# nrf52_dev.net
KiCad netlist of a schematic drawn in EAGLE
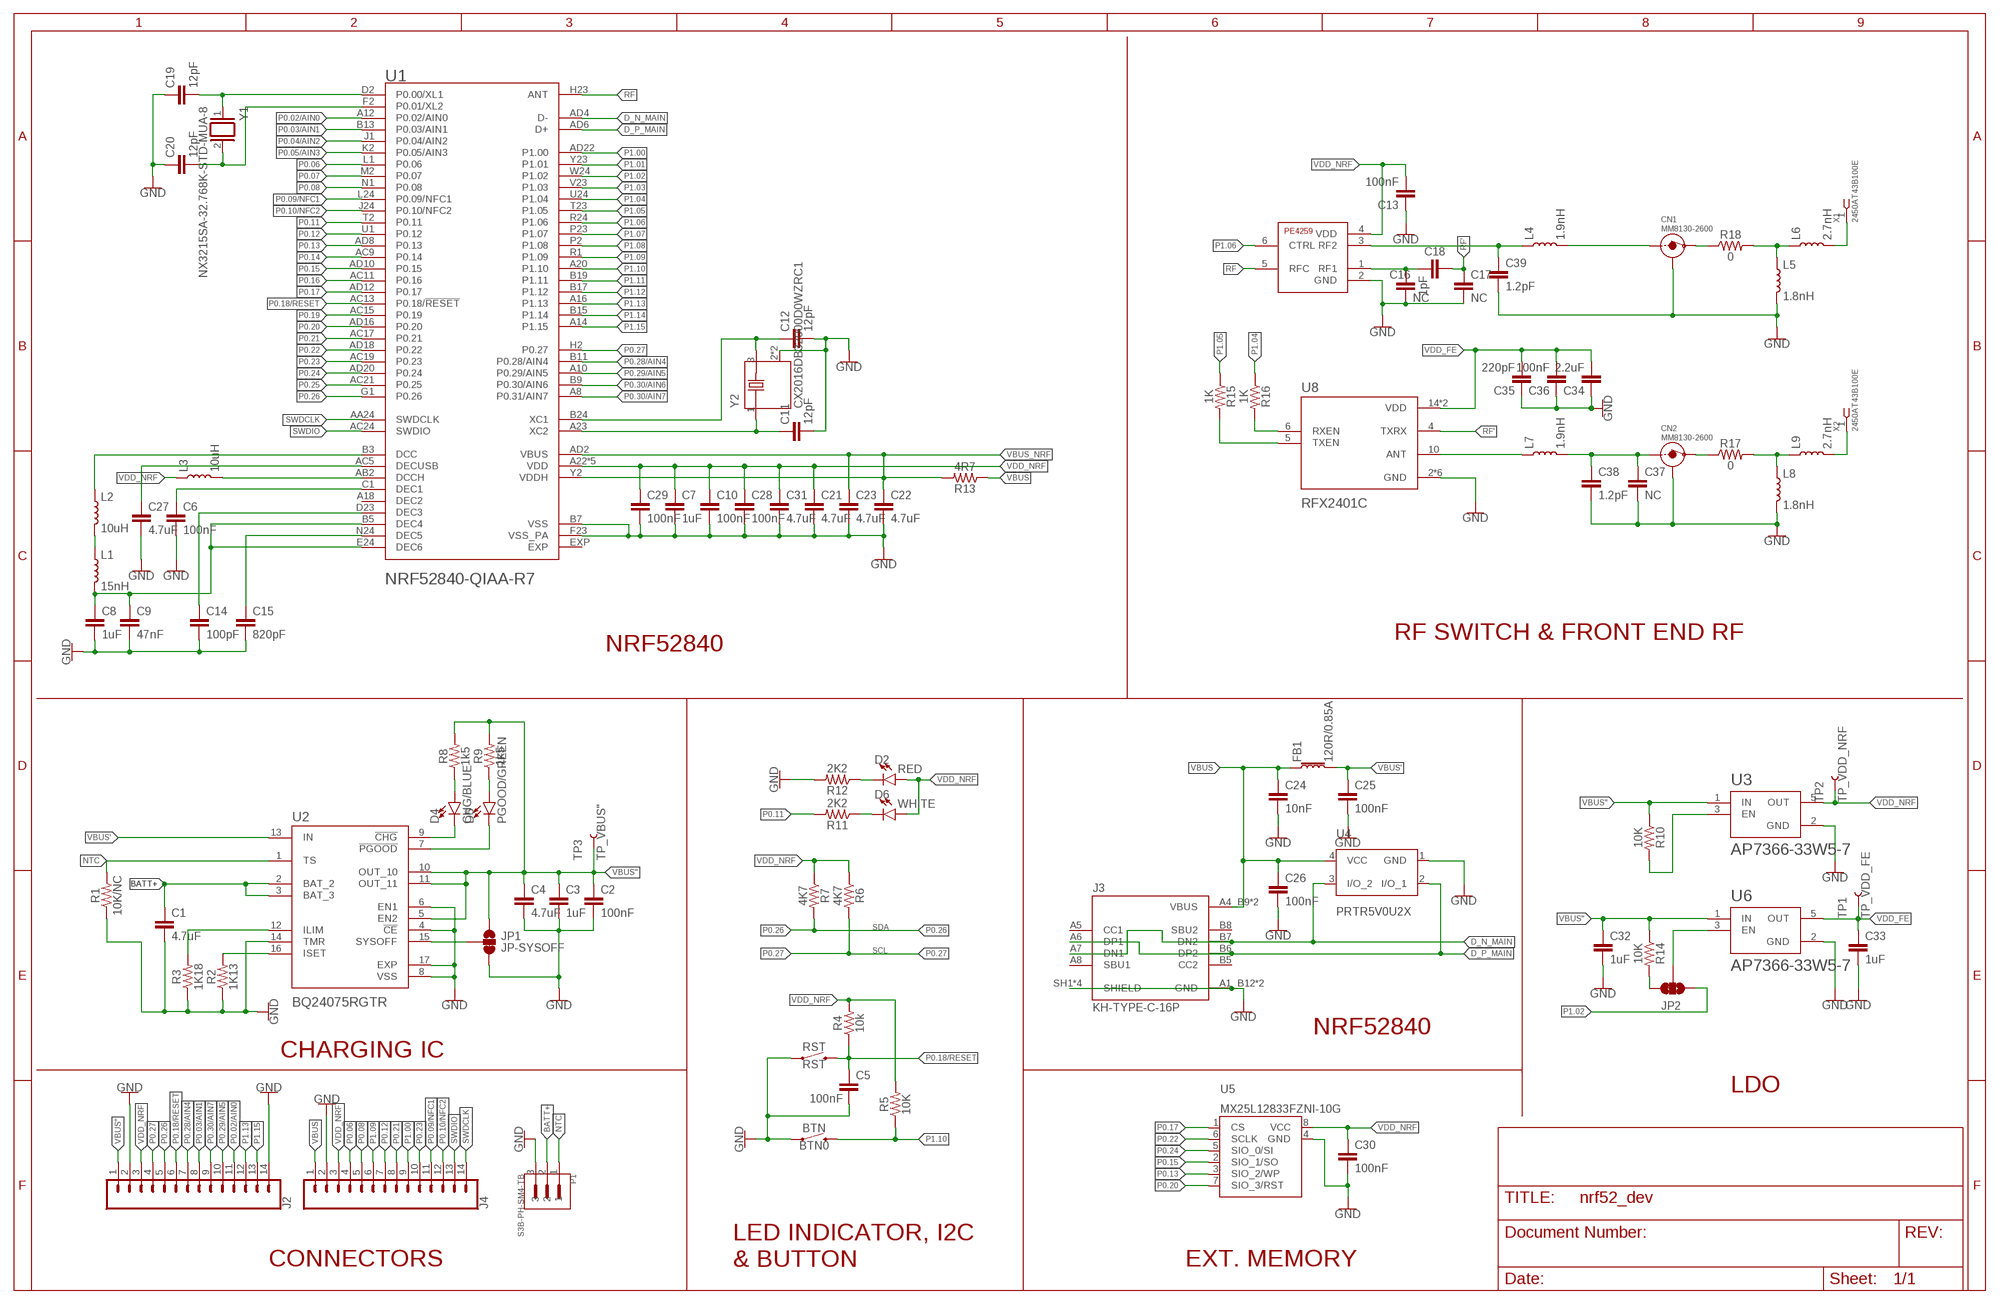
[diagram p0: schematic, sheet 1]

(export (version "E")
  (design (tool "Eeschema 10.0.6"))
  (components
    (comp (ref "BTN")
      (value "BTN0")
      (footprint "eagle-import:TACTILE_SWITCH_SMD_6.0X3.5MM")
      (libsource (lib "eagle-import") (part "MOMENTARY-SWITCH-SPST-SMD-6.0X3.5MM"))
    )
    (comp (ref "C1")
      (value "4.7uF")
      (footprint "eagle-import:0805")
      (libsource (lib "eagle-import") (part "4.7UF-0805-50V-(10%)"))
    )
    (comp (ref "C2")
      (value "100nF")
      (footprint "eagle-import:0603")
      (libsource (lib "eagle-import") (part "0.1UF-0603-25V-(+80/-20%)"))
    )
    (comp (ref "C3")
      (value "1uF")
      (footprint "eagle-import:0603")
      (libsource (lib "eagle-import") (part "0.1UF-0603-25V-(+80/-20%)"))
    )
    (comp (ref "C4")
      (value "4.7uF")
      (footprint "eagle-import:0805")
      (libsource (lib "eagle-import") (part "4.7UF-0805-50V-(10%)"))
    )
    (comp (ref "C5")
      (value "100nF")
      (footprint "eagle-import:0402")
      (libsource (lib "eagle-import") (part "0.1UF-0402-10V-10%-X7R"))
    )
    (comp (ref "C6")
      (value "100nF")
      (footprint "eagle-import:0402")
      (libsource (lib "eagle-import") (part "0.1UF-0402-10V-10%-X7R"))
    )
    (comp (ref "C7")
      (value "1uF")
      (footprint "eagle-import:0402")
      (libsource (lib "eagle-import") (part "0.1UF-0402-10V-10%-X7R"))
    )
    (comp (ref "C8")
      (value "1uF")
      (footprint "eagle-import:0402")
      (libsource (lib "eagle-import") (part "0.1UF-0402-10V-10%-X7R"))
    )
    (comp (ref "C9")
      (value "47nF")
      (footprint "eagle-import:0402")
      (libsource (lib "eagle-import") (part "0.1UF-0402-10V-10%-X7R"))
    )
    (comp (ref "C10")
      (value "100nF")
      (footprint "eagle-import:0402")
      (libsource (lib "eagle-import") (part "0.1UF-0402-10V-10%-X7R"))
    )
    (comp (ref "C11")
      (value "12pF")
      (footprint "eagle-import:0603")
      (libsource (lib "eagle-import") (part "0.1UF-0603-25V-(+80/-20%)"))
    )
    (comp (ref "C12")
      (value "12pF")
      (footprint "eagle-import:0603")
      (libsource (lib "eagle-import") (part "0.1UF-0603-25V-(+80/-20%)"))
    )
    (comp (ref "C13")
      (value "100nF")
      (footprint "eagle-import:0402")
      (libsource (lib "eagle-import") (part "0.1UF-0402-10V-10%-X7R"))
    )
    (comp (ref "C14")
      (value "100pF")
      (footprint "eagle-import:0402")
      (libsource (lib "eagle-import") (part "0.1UF-0402-10V-10%-X7R"))
    )
    (comp (ref "C15")
      (value "820pF")
      (footprint "eagle-import:0402")
      (libsource (lib "eagle-import") (part "0.1UF-0402-10V-10%-X7R"))
    )
    (comp (ref "C16")
      (value "NC")
      (footprint "eagle-import:0402")
      (libsource (lib "eagle-import") (part "0.1UF-0402-10V-10%-X7R"))
    )
    (comp (ref "C17")
      (value "NC")
      (footprint "eagle-import:0402")
      (libsource (lib "eagle-import") (part "0.1UF-0402-10V-10%-X7R"))
    )
    (comp (ref "C18")
      (value "1pF")
      (footprint "eagle-import:0603")
      (libsource (lib "eagle-import") (part "0.1UF-0603-25V-(+80/-20%)"))
    )
    (comp (ref "C19")
      (value "12pF")
      (footprint "eagle-import:0402")
      (libsource (lib "eagle-import") (part "0.1UF-0402-10V-10%-X7R"))
    )
    (comp (ref "C20")
      (value "12pF")
      (footprint "eagle-import:0402")
      (libsource (lib "eagle-import") (part "0.1UF-0402-10V-10%-X7R"))
    )
    (comp (ref "C21")
      (value "4.7uF")
      (footprint "eagle-import:0402")
      (libsource (lib "eagle-import") (part "0.1UF-0402-10V-10%-X7R"))
    )
    (comp (ref "C22")
      (value "4.7uF")
      (footprint "eagle-import:0402")
      (libsource (lib "eagle-import") (part "0.1UF-0402-10V-10%-X7R"))
    )
    (comp (ref "C23")
      (value "4.7uF")
      (footprint "eagle-import:0402")
      (libsource (lib "eagle-import") (part "0.1UF-0402-10V-10%-X7R"))
    )
    (comp (ref "C24")
      (value "10nF")
      (footprint "eagle-import:0402")
      (libsource (lib "eagle-import") (part "0.1UF-0402-10V-10%-X7R"))
    )
    (comp (ref "C25")
      (value "100nF")
      (footprint "eagle-import:0402")
      (libsource (lib "eagle-import") (part "0.1UF-0402-10V-10%-X7R"))
    )
    (comp (ref "C26")
      (value "100nF")
      (footprint "eagle-import:0402")
      (libsource (lib "eagle-import") (part "0.1UF-0402-10V-10%-X7R"))
    )
    (comp (ref "C27")
      (value "4.7uF")
      (footprint "eagle-import:0603")
      (libsource (lib "eagle-import") (part "0.1UF-0603-25V-(+80/-20%)"))
    )
    (comp (ref "C28")
      (value "100nF")
      (footprint "eagle-import:0402")
      (libsource (lib "eagle-import") (part "0.1UF-0402-10V-10%-X7R"))
    )
    (comp (ref "C29")
      (value "100nF")
      (footprint "eagle-import:0402")
      (libsource (lib "eagle-import") (part "0.1UF-0402-10V-10%-X7R"))
    )
    (comp (ref "C30")
      (value "100nF")
      (footprint "eagle-import:0402")
      (libsource (lib "eagle-import") (part "0.1UF-0402-10V-10%-X7R"))
    )
    (comp (ref "C31")
      (value "4.7uF")
      (footprint "eagle-import:0402")
      (libsource (lib "eagle-import") (part "0.1UF-0402-10V-10%-X7R"))
    )
    (comp (ref "C32")
      (value "1uF")
      (footprint "eagle-import:0603")
      (libsource (lib "eagle-import") (part "0.1UF-0603-25V-(+80/-20%)"))
    )
    (comp (ref "C33")
      (value "1uF")
      (footprint "eagle-import:0603")
      (libsource (lib "eagle-import") (part "0.1UF-0603-25V-(+80/-20%)"))
    )
    (comp (ref "C34")
      (value "2.2uF")
      (footprint "eagle-import:0402")
      (libsource (lib "eagle-import") (part "0.1UF-0402-10V-10%-X7R"))
    )
    (comp (ref "C35")
      (value "220pF")
      (footprint "eagle-import:0402")
      (libsource (lib "eagle-import") (part "0.1UF-0402-10V-10%-X7R"))
    )
    (comp (ref "C36")
      (value "100nF")
      (footprint "eagle-import:0402")
      (libsource (lib "eagle-import") (part "0.1UF-0402-10V-10%-X7R"))
    )
    (comp (ref "C37")
      (value "NC")
      (footprint "eagle-import:0402")
      (libsource (lib "eagle-import") (part "0.1UF-0402-10V-10%-X7R"))
    )
    (comp (ref "C38")
      (value "1.2pF")
      (footprint "eagle-import:0402")
      (libsource (lib "eagle-import") (part "0.1UF-0402-10V-10%-X7R"))
    )
    (comp (ref "C39")
      (value "1.2pF")
      (footprint "eagle-import:0402")
      (libsource (lib "eagle-import") (part "0.1UF-0402-10V-10%-X7R"))
    )
    (comp (ref "CN1")
      (value "MM8130-2600")
      (footprint "eagle-import:MM8130-2600")
      (fields (field (name "MF") "Murata"))
      (libsource (lib "eagle-import") (part "MM8130-2600"))
    )
    (comp (ref "CN2")
      (value "MM8130-2600")
      (footprint "eagle-import:MM8130-2600")
      (fields (field (name "MF") "Murata"))
      (libsource (lib "eagle-import") (part "MM8130-2600"))
    )
    (comp (ref "D2")
      (value "RED")
      (footprint "eagle-import:LED-0603")
      (libsource (lib "eagle-import") (part "LED0603"))
    )
    (comp (ref "D4")
      (value "CHG/BLUE")
      (footprint "eagle-import:LED-0603")
      (libsource (lib "eagle-import") (part "LED0603"))
    )
    (comp (ref "D5")
      (value "PGOOD/GREEN")
      (footprint "eagle-import:LED-0603")
      (libsource (lib "eagle-import") (part "LED0603"))
    )
    (comp (ref "D6")
      (value "WHITE")
      (footprint "eagle-import:LED-0603")
      (libsource (lib "eagle-import") (part "LED0603"))
    )
    (comp (ref "FB1")
      (value "120R/0.85A")
      (footprint "eagle-import:0402")
      (libsource (lib "eagle-import") (part "FERRITE_BEAD"))
    )
    (comp (ref "J2")
      (value "CONN_14NO_SILK")
      (footprint "eagle-import:1X14_NO_SILK")
      (libsource (lib "eagle-import") (part "CONN_14NO_SILK"))
    )
    (comp (ref "J3")
      (value "KH-TYPE-C-16P")
      (footprint "eagle-import:KINGHELM_KH-TYPE-C-16P")
      (fields (field (name "MF") "kinghelm"))
      (libsource (lib "eagle-import") (part "KH-TYPE-C-16P"))
    )
    (comp (ref "J4")
      (value "CONN_14NO_SILK")
      (footprint "eagle-import:1X14_NO_SILK")
      (libsource (lib "eagle-import") (part "CONN_14NO_SILK"))
    )
    (comp (ref "JP1")
      (value "JP-SYSOFF")
      (footprint "eagle-import:SMT-JUMPER_3_1-NC_TRACE_SILK")
      (libsource (lib "eagle-import") (part "JUMPER-SMT_3_1-NC_TRACE_SILK"))
    )
    (comp (ref "JP2")
      (value "JP_EN1")
      (footprint "eagle-import:SMT-JUMPER_3_1-NC_TRACE_SILK")
      (libsource (lib "eagle-import") (part "JUMPER-SMT_3_1-NC_TRACE_SILK"))
    )
    (comp (ref "L1")
      (value "15nH")
      (footprint "eagle-import:0402")
      (libsource (lib "eagle-import") (part "INDUCTOR-0402-3.9NH"))
    )
    (comp (ref "L2")
      (value "10uH")
      (footprint "eagle-import:0603")
      (libsource (lib "eagle-import") (part "39NH-0603"))
    )
    (comp (ref "L3")
      (value "10uH")
      (footprint "eagle-import:0603")
      (libsource (lib "eagle-import") (part "39NH-0603"))
    )
    (comp (ref "L4")
      (value "1.9nH")
      (footprint "eagle-import:0402")
      (libsource (lib "eagle-import") (part "INDUCTOR-0402-3.9NH"))
    )
    (comp (ref "L5")
      (value "1.8nH")
      (footprint "eagle-import:0603")
      (libsource (lib "eagle-import") (part "39NH-0603"))
    )
    (comp (ref "L6")
      (value "2.7nH")
      (footprint "eagle-import:0603")
      (libsource (lib "eagle-import") (part "39NH-0603"))
    )
    (comp (ref "L7")
      (value "1.9nH")
      (footprint "eagle-import:0402")
      (libsource (lib "eagle-import") (part "INDUCTOR-0402-3.9NH"))
    )
    (comp (ref "L8")
      (value "1.8nH")
      (footprint "eagle-import:0603")
      (libsource (lib "eagle-import") (part "39NH-0603"))
    )
    (comp (ref "L9")
      (value "2.7nH")
      (footprint "eagle-import:0603")
      (libsource (lib "eagle-import") (part "39NH-0603"))
    )
    (comp (ref "P1")
      (value "S3B-PH-SM4-TB")
      (footprint "eagle-import:JST_S3B-PH-SM4-TB")
      (fields (field (name "MF") "JST Sales"))
      (libsource (lib "eagle-import") (part "S3B-PH-SM4-TB"))
    )
    (comp (ref "R1")
      (value "10K/NC")
      (footprint "eagle-import:0603")
      (libsource (lib "eagle-import") (part "RESISTOR0603"))
    )
    (comp (ref "R2")
      (value "1K13")
      (footprint "eagle-import:0603")
      (libsource (lib "eagle-import") (part "RESISTOR0603"))
    )
    (comp (ref "R3")
      (value "1K18")
      (footprint "eagle-import:0603")
      (libsource (lib "eagle-import") (part "RESISTOR0603"))
    )
    (comp (ref "R4")
      (value "10k")
      (footprint "eagle-import:0402")
      (libsource (lib "eagle-import") (part "RESISTOR0402"))
    )
    (comp (ref "R5")
      (value "10K")
      (footprint "eagle-import:0402")
      (libsource (lib "eagle-import") (part "RESISTOR0402"))
    )
    (comp (ref "R6")
      (value "4K7")
      (footprint "eagle-import:0402")
      (libsource (lib "eagle-import") (part "0OHM-0402-1/10W"))
    )
    (comp (ref "R7")
      (value "4K7")
      (footprint "eagle-import:0402")
      (libsource (lib "eagle-import") (part "0OHM-0402-1/10W"))
    )
    (comp (ref "R8")
      (value "1k5")
      (footprint "eagle-import:0402")
      (libsource (lib "eagle-import") (part "0OHM-0402-1/10W"))
    )
    (comp (ref "R9")
      (value "1k5")
      (footprint "eagle-import:0402")
      (libsource (lib "eagle-import") (part "0OHM-0402-1/10W"))
    )
    (comp (ref "R10")
      (value "10K")
      (footprint "eagle-import:0603")
      (libsource (lib "eagle-import") (part "RESISTOR0603"))
    )
    (comp (ref "R11")
      (value "2K2")
      (footprint "eagle-import:0402")
      (libsource (lib "eagle-import") (part "0OHM-0402-1/10W"))
    )
    (comp (ref "R12")
      (value "2K2")
      (footprint "eagle-import:0402")
      (libsource (lib "eagle-import") (part "0OHM-0402-1/10W"))
    )
    (comp (ref "R13")
      (value "4R7")
      (footprint "eagle-import:0603")
      (libsource (lib "eagle-import") (part "RESISTOR0603"))
    )
    (comp (ref "R14")
      (value "10K")
      (footprint "eagle-import:0603")
      (libsource (lib "eagle-import") (part "RESISTOR0603"))
    )
    (comp (ref "R15")
      (value "1K")
      (footprint "eagle-import:0402")
      (libsource (lib "eagle-import") (part "0OHM-0402-1/10W"))
    )
    (comp (ref "R16")
      (value "1K")
      (footprint "eagle-import:0402")
      (libsource (lib "eagle-import") (part "0OHM-0402-1/10W"))
    )
    (comp (ref "R17")
      (value "0")
      (footprint "eagle-import:0402")
      (libsource (lib "eagle-import") (part "0OHM-0402-1/10W"))
    )
    (comp (ref "R18")
      (value "0")
      (footprint "eagle-import:0402")
      (libsource (lib "eagle-import") (part "0OHM-0402-1/10W"))
    )
    (comp (ref "RST")
      (value "RST")
      (footprint "eagle-import:TACTILE_SWITCH_SMD_6.0X3.5MM")
      (libsource (lib "eagle-import") (part "MOMENTARY-SWITCH-SPST-SMD-6.0X3.5MM"))
    )
    (comp (ref "TP1")
      (value "TP_VDD_FE")
      (footprint "eagle-import:PAD.03X.04")
      (libsource (lib "eagle-import") (part "TEST-POINT3X4"))
    )
    (comp (ref "TP2")
      (value "TP_VDD_NRF")
      (footprint "eagle-import:PAD.03X.04")
      (libsource (lib "eagle-import") (part "TEST-POINT3X4"))
    )
    (comp (ref "TP3")
      (value "TP_VBUS''")
      (footprint "eagle-import:PAD.03X.04")
      (libsource (lib "eagle-import") (part "TEST-POINT3X4"))
    )
    (comp (ref "U1")
      (value "NRF52840-QIAA-R7")
      (footprint "eagle-import:NORDIC_NRF52840-QIAA-R7")
      (fields (field (name "MF") "Nordic Semiconductor"))
      (libsource (lib "eagle-import") (part "NRF52840-QIAA-R7"))
    )
    (comp (ref "U2")
      (value "BQ24075RGTR")
      (footprint "eagle-import:QFN50P300X300X100-17N")
      (fields (field (name "DIGI-KEY_PART_NUMBER") "296-38874-2-ND") (field (name "MF") "Texas Instruments"))
      (libsource (lib "eagle-import") (part "BQ24075RGTR"))
    )
    (comp (ref "U3")
      (value "AP7366-33W5-7")
      (footprint "eagle-import:SOT95P285X140-5N")
      (fields (field (name "MF") "Diodes Zetex"))
      (libsource (lib "eagle-import") (part "AP7366-33W5-7"))
    )
    (comp (ref "U4")
      (value "PRTR5V0U2X")
      (footprint "eagle-import:SOT190P230X110-4N")
      (fields (field (name "MF") "Nexperia USA"))
      (libsource (lib "eagle-import") (part "PRTR5V0U2X"))
    )
    (comp (ref "U5")
      (value "MX25L12833FZNI-10G")
      (footprint "eagle-import:SON127P500X600X80-9N")
      (libsource (lib "eagle-import") (part "MX25L12833FZNI-10G"))
    )
    (comp (ref "U6")
      (value "AP7366-33W5-7")
      (footprint "eagle-import:SOT95P285X140-5N")
      (fields (field (name "MF") "Diodes Zetex"))
      (libsource (lib "eagle-import") (part "AP7366-33W5-7"))
    )
    (comp (ref "U7")
      (value "PE4259")
      (footprint "eagle-import:SOT65P210X110-6N")
      (libsource (lib "eagle-import") (part "PE4259"))
    )
    (comp (ref "U8")
      (value "RFX2401C")
      (footprint "eagle-import:QFN50P300X300X60-17N")
      (fields (field (name "MF") "Skyworks Solutions"))
      (libsource (lib "eagle-import") (part "RFX2401C"))
    )
    (comp (ref "X1")
      (value "2450AT43B100E")
      (footprint "eagle-import:2450AT43B100")
      (fields (field (name "MF") "Johanson"))
      (libsource (lib "eagle-import") (part "2450AT43B100E"))
    )
    (comp (ref "X2")
      (value "2450AT43B100E")
      (footprint "eagle-import:2450AT43B100")
      (fields (field (name "MF") "Johanson"))
      (libsource (lib "eagle-import") (part "2450AT43B100E"))
    )
    (comp (ref "Y1")
      (value "NX3215SA-32.768K-STD-MUA-8")
      (footprint "eagle-import:XTAL_NX3215SA-32.768K-STD-MUA-8")
      (fields (field (name "DIGI-KEY_PART_NUMBER") "644-1156-2-ND") (field (name "MF") "NDK America,"))
      (libsource (lib "eagle-import") (part "NX3215SA-32.768K-STD-MUA-8"))
    )
    (comp (ref "Y2")
      (value "CX2016DB32000D0WZRC1")
      (footprint "eagle-import:OSCCC200X160X45N")
      (fields (field (name "MF") "Kyocera International"))
      (libsource (lib "eagle-import") (part "CX2016DB32000D0WZRC1"))
    )
  )
  (nets
    (net (code "1") (name "/DEC2") (class "Default")
      (node (ref "U1") (pin "A18") (pinfunction "DEC2_A18") (pintype "power_in"))
    )
    (net (code "2") (name "/EXP") (class "Default")
      (node (ref "U1") (pin "EXP") (pinfunction "EXP_EXP") (pintype "power_in"))
    )
    (net (code "3") (name "BATT+") (class "Default")
      (node (ref "C1") (pin "1") (pinfunction "1_1") (pintype "passive"))
      (node (ref "P1") (pin "2") (pinfunction "2_2") (pintype "passive"))
      (node (ref "U2") (pin "2") (pinfunction "BAT_2_2") (pintype "bidirectional"))
      (node (ref "U2") (pin "3") (pinfunction "BAT_3_3") (pintype "bidirectional"))
    )
    (net (code "4") (name "D_N_MAIN") (class "Default")
      (node (ref "J3") (pin "A7") (pinfunction "DN1_A7") (pintype "bidirectional"))
      (node (ref "J3") (pin "B7") (pinfunction "DN2_B7") (pintype "bidirectional"))
      (node (ref "U1") (pin "AD4") (pinfunction "D-_AD4") (pintype "bidirectional"))
      (node (ref "U4") (pin "3") (pinfunction "I/O_2_3") (pintype "passive"))
    )
    (net (code "5") (name "D_P_MAIN") (class "Default")
      (node (ref "J3") (pin "A6") (pinfunction "DP1_A6") (pintype "bidirectional"))
      (node (ref "J3") (pin "B6") (pinfunction "DP2_B6") (pintype "bidirectional"))
      (node (ref "U1") (pin "AD6") (pinfunction "D+_AD6") (pintype "bidirectional"))
      (node (ref "U4") (pin "2") (pinfunction "I/O_1_2") (pintype "passive"))
    )
    (net (code "6") (name "GND") (class "Default")
      (node (ref "BTN") (pin "1") (pinfunction "1_1") (pintype "passive"))
      (node (ref "C1") (pin "2") (pinfunction "2_2") (pintype "passive"))
      (node (ref "C10") (pin "2") (pinfunction "2_2") (pintype "passive"))
      (node (ref "C11") (pin "2") (pinfunction "2_2") (pintype "passive"))
      (node (ref "C12") (pin "2") (pinfunction "2_2") (pintype "passive"))
      (node (ref "C13") (pin "1") (pinfunction "1_1") (pintype "passive"))
      (node (ref "C14") (pin "2") (pinfunction "2_2") (pintype "passive"))
      (node (ref "C15") (pin "2") (pinfunction "2_2") (pintype "passive"))
      (node (ref "C16") (pin "2") (pinfunction "2_2") (pintype "passive"))
      (node (ref "C17") (pin "2") (pinfunction "2_2") (pintype "passive"))
      (node (ref "C19") (pin "1") (pinfunction "1_1") (pintype "passive"))
      (node (ref "C2") (pin "2") (pinfunction "2_2") (pintype "passive"))
      (node (ref "C20") (pin "1") (pinfunction "1_1") (pintype "passive"))
      (node (ref "C21") (pin "2") (pinfunction "2_2") (pintype "passive"))
      (node (ref "C22") (pin "2") (pinfunction "2_2") (pintype "passive"))
      (node (ref "C23") (pin "2") (pinfunction "2_2") (pintype "passive"))
      (node (ref "C24") (pin "2") (pinfunction "2_2") (pintype "passive"))
      (node (ref "C25") (pin "2") (pinfunction "2_2") (pintype "passive"))
      (node (ref "C26") (pin "2") (pinfunction "2_2") (pintype "passive"))
      (node (ref "C27") (pin "2") (pinfunction "2_2") (pintype "passive"))
      (node (ref "C28") (pin "2") (pinfunction "2_2") (pintype "passive"))
      (node (ref "C29") (pin "2") (pinfunction "2_2") (pintype "passive"))
      (node (ref "C3") (pin "2") (pinfunction "2_2") (pintype "passive"))
      (node (ref "C30") (pin "2") (pinfunction "2_2") (pintype "passive"))
      (node (ref "C31") (pin "2") (pinfunction "2_2") (pintype "passive"))
      (node (ref "C32") (pin "2") (pinfunction "2_2") (pintype "passive"))
      (node (ref "C33") (pin "2") (pinfunction "2_2") (pintype "passive"))
      (node (ref "C34") (pin "1") (pinfunction "1_1") (pintype "passive"))
      (node (ref "C35") (pin "1") (pinfunction "1_1") (pintype "passive"))
      (node (ref "C36") (pin "1") (pinfunction "1_1") (pintype "passive"))
      (node (ref "C37") (pin "2") (pinfunction "2_2") (pintype "passive"))
      (node (ref "C38") (pin "2") (pinfunction "2_2") (pintype "passive"))
      (node (ref "C39") (pin "2") (pinfunction "2_2") (pintype "passive"))
      (node (ref "C4") (pin "2") (pinfunction "2_2") (pintype "passive"))
      (node (ref "C5") (pin "2") (pinfunction "2_2") (pintype "passive"))
      (node (ref "C6") (pin "2") (pinfunction "2_2") (pintype "passive"))
      (node (ref "C7") (pin "2") (pinfunction "2_2") (pintype "passive"))
      (node (ref "C8") (pin "2") (pinfunction "2_2") (pintype "passive"))
      (node (ref "C9") (pin "2") (pinfunction "2_2") (pintype "passive"))
      (node (ref "CN1") (pin "1") (pintype "passive"))
      (node (ref "CN1") (pin "2") (pintype "passive"))
      (node (ref "CN1") (pin "3") (pintype "passive"))
      (node (ref "CN1") (pin "4") (pintype "passive"))
      (node (ref "CN2") (pin "1") (pintype "passive"))
      (node (ref "CN2") (pin "2") (pintype "passive"))
      (node (ref "CN2") (pin "3") (pintype "passive"))
      (node (ref "CN2") (pin "4") (pintype "passive"))
      (node (ref "J2") (pin "14") (pinfunction "14_14") (pintype "passive"))
      (node (ref "J2") (pin "2") (pinfunction "2_2") (pintype "passive"))
      (node (ref "J3") (pin "A12_B1") (pinfunction "GND_A12_B1") (pintype "power_in"))
      (node (ref "J3") (pin "A1_B12") (pinfunction "GND_A1_B12") (pintype "power_in"))
      (node (ref "J3") (pin "SH1") (pinfunction "SHIELD_SH1") (pintype "passive"))
      (node (ref "J3") (pin "SH2") (pinfunction "SHIELD_SH2") (pintype "passive"))
      (node (ref "J3") (pin "SH3") (pinfunction "SHIELD_SH3") (pintype "passive"))
      (node (ref "J3") (pin "SH4") (pinfunction "SHIELD_SH4") (pintype "passive"))
      (node (ref "J4") (pin "2") (pinfunction "2_2") (pintype "passive"))
      (node (ref "JP1") (pin "3") (pinfunction "3_3") (pintype "passive"))
      (node (ref "L5") (pin "2") (pinfunction "2_2") (pintype "passive"))
      (node (ref "L8") (pin "2") (pinfunction "2_2") (pintype "passive"))
      (node (ref "P1") (pin "3") (pinfunction "3_3") (pintype "passive"))
      (node (ref "R1") (pin "1") (pinfunction "1_1") (pintype "passive"))
      (node (ref "R12") (pin "2") (pinfunction "2_2") (pintype "passive"))
      (node (ref "R2") (pin "1") (pinfunction "1_1") (pintype "passive"))
      (node (ref "R3") (pin "1") (pinfunction "1_1") (pintype "passive"))
      (node (ref "RST") (pin "1") (pinfunction "1_1") (pintype "passive"))
      (node (ref "U1") (pin "B7") (pinfunction "VSS_B7") (pintype "power_in"))
      (node (ref "U1") (pin "F23") (pinfunction "VSS_PA_F23") (pintype "power_in"))
      (node (ref "U2") (pin "14") (pinfunction "TMR_14") (pintype "input"))
      (node (ref "U2") (pin "17") (pinfunction "EXP_17") (pintype "power_in"))
      (node (ref "U2") (pin "4") (pinfunction "~{CE}_4") (pintype "input"))
      (node (ref "U2") (pin "6") (pinfunction "EN1_6") (pintype "input"))
      (node (ref "U2") (pin "8") (pinfunction "VSS_8") (pintype "power_in"))
      (node (ref "U3") (pin "2") (pinfunction "GND_2") (pintype "power_in"))
      (node (ref "U4") (pin "1") (pinfunction "GND_1") (pintype "passive"))
      (node (ref "U5") (pin "4") (pinfunction "GND_4") (pintype "power_in"))
      (node (ref "U6") (pin "2") (pinfunction "GND_2") (pintype "power_in"))
      (node (ref "U7") (pin "2") (pinfunction "GND_2") (pintype "bidirectional"))
      (node (ref "U8") (pin "11") (pinfunction "GND_11") (pintype "power_in"))
      (node (ref "U8") (pin "17") (pinfunction "GND_17") (pintype "power_in"))
      (node (ref "U8") (pin "2") (pinfunction "GND_2") (pintype "power_in"))
      (node (ref "U8") (pin "3") (pinfunction "GND_3") (pintype "power_in"))
      (node (ref "U8") (pin "8") (pinfunction "GND_8") (pintype "power_in"))
      (node (ref "U8") (pin "9") (pinfunction "GND_9") (pintype "power_in"))
      (node (ref "Y2") (pin "2") (pinfunction "GND_2") (pintype "power_in"))
      (node (ref "Y2") (pin "4") (pinfunction "GND_4") (pintype "power_in"))
    )
    (net (code "7") (name "NTC") (class "Default")
      (node (ref "P1") (pin "1") (pinfunction "1_1") (pintype "passive"))
      (node (ref "R1") (pin "2") (pinfunction "2_2") (pintype "passive"))
      (node (ref "U2") (pin "1") (pinfunction "TS_1") (pintype "input"))
    )
    (net (code "8") (name "Net-(C37-Pad1)") (class "Default")
      (node (ref "C37") (pin "1") (pinfunction "1_1") (pintype "passive"))
      (node (ref "C38") (pin "1") (pinfunction "1_1") (pintype "passive"))
      (node (ref "CN2") (pin "IN") (pintype "passive"))
      (node (ref "L7") (pin "2") (pinfunction "2_2") (pintype "passive"))
    )
    (net (code "9") (name "Net-(CN1-PadIN)") (class "Default")
      (node (ref "CN1") (pin "IN") (pintype "passive"))
      (node (ref "L4") (pin "2") (pinfunction "2_2") (pintype "passive"))
    )
    (net (code "10") (name "Net-(CN1-PadOUT)") (class "Default")
      (node (ref "CN1") (pin "OUT") (pintype "passive"))
      (node (ref "R18") (pin "1") (pinfunction "1_1") (pintype "passive"))
    )
    (net (code "11") (name "Net-(CN2-PadOUT)") (class "Default")
      (node (ref "CN2") (pin "OUT") (pintype "passive"))
      (node (ref "R17") (pin "1") (pinfunction "1_1") (pintype "passive"))
    )
    (net (code "12") (name "Net-(D2-PadC)") (class "Default")
      (node (ref "D2") (pin "C") (pinfunction "C_C") (pintype "passive"))
      (node (ref "R12") (pin "1") (pinfunction "1_1") (pintype "passive"))
    )
    (net (code "13") (name "Net-(D4-PadA)") (class "Default")
      (node (ref "D4") (pin "A") (pinfunction "A_A") (pintype "passive"))
      (node (ref "R8") (pin "1") (pinfunction "1_1") (pintype "passive"))
    )
    (net (code "14") (name "Net-(D5-PadA)") (class "Default")
      (node (ref "D5") (pin "A") (pinfunction "A_A") (pintype "passive"))
      (node (ref "R9") (pin "1") (pinfunction "1_1") (pintype "passive"))
    )
    (net (code "15") (name "Net-(D6-PadC)") (class "Default")
      (node (ref "D6") (pin "C") (pinfunction "C_C") (pintype "passive"))
      (node (ref "R11") (pin "1") (pinfunction "1_1") (pintype "passive"))
    )
    (net (code "16") (name "Net-(JP2-Pad3)") (class "Default")
      (node (ref "JP2") (pin "3") (pinfunction "3_3") (pintype "passive"))
      (node (ref "R14") (pin "2") (pinfunction "2_2") (pintype "passive"))
    )
    (net (code "17") (name "Net-(L1-Pad1)") (class "Default")
      (node (ref "L1") (pin "1") (pinfunction "1_1") (pintype "passive"))
      (node (ref "L2") (pin "2") (pinfunction "2_2") (pintype "passive"))
    )
    (net (code "18") (name "Net-(L5-Pad1)") (class "Default")
      (node (ref "L5") (pin "1") (pinfunction "1_1") (pintype "passive"))
      (node (ref "L6") (pin "1") (pinfunction "1_1") (pintype "passive"))
      (node (ref "R18") (pin "2") (pinfunction "2_2") (pintype "passive"))
    )
    (net (code "19") (name "Net-(L6-Pad2)") (class "Default")
      (node (ref "L6") (pin "2") (pinfunction "2_2") (pintype "passive"))
      (node (ref "X1") (pin "1") (pinfunction "1_1") (pintype "passive"))
    )
    (net (code "20") (name "Net-(L8-Pad1)") (class "Default")
      (node (ref "L8") (pin "1") (pinfunction "1_1") (pintype "passive"))
      (node (ref "L9") (pin "1") (pinfunction "1_1") (pintype "passive"))
      (node (ref "R17") (pin "2") (pinfunction "2_2") (pintype "passive"))
    )
    (net (code "21") (name "Net-(L9-Pad2)") (class "Default")
      (node (ref "L9") (pin "2") (pinfunction "2_2") (pintype "passive"))
      (node (ref "X2") (pin "1") (pinfunction "1_1") (pintype "passive"))
    )
    (net (code "22") (name "Net-(U1-DCC)") (class "Default")
      (node (ref "L2") (pin "1") (pinfunction "1_1") (pintype "passive"))
      (node (ref "U1") (pin "B3") (pinfunction "DCC_B3") (pintype "power_in"))
    )
    (net (code "23") (name "Net-(U1-DCCH)") (class "Default")
      (node (ref "L3") (pin "2") (pinfunction "2_2") (pintype "passive"))
      (node (ref "U1") (pin "AB2") (pinfunction "DCCH_AB2") (pintype "power_in"))
    )
    (net (code "24") (name "Net-(U1-DEC1)") (class "Default")
      (node (ref "C6") (pin "1") (pinfunction "1_1") (pintype "passive"))
      (node (ref "U1") (pin "C1") (pinfunction "DEC1_C1") (pintype "power_in"))
    )
    (net (code "25") (name "Net-(U1-DEC3)") (class "Default")
      (node (ref "C14") (pin "1") (pinfunction "1_1") (pintype "passive"))
      (node (ref "U1") (pin "D23") (pinfunction "DEC3_D23") (pintype "power_in"))
    )
    (net (code "26") (name "Net-(U1-DEC4)") (class "Default")
      (node (ref "C8") (pin "1") (pinfunction "1_1") (pintype "passive"))
      (node (ref "C9") (pin "1") (pinfunction "1_1") (pintype "passive"))
      (node (ref "L1") (pin "2") (pinfunction "2_2") (pintype "passive"))
      (node (ref "U1") (pin "B5") (pinfunction "DEC4_B5") (pintype "power_in"))
      (node (ref "U1") (pin "E24") (pinfunction "DEC6_E24") (pintype "power_in"))
    )
    (net (code "27") (name "Net-(U1-DEC5)") (class "Default")
      (node (ref "C15") (pin "1") (pinfunction "1_1") (pintype "passive"))
      (node (ref "U1") (pin "N24") (pinfunction "DEC5_N24") (pintype "power_in"))
    )
    (net (code "28") (name "Net-(U1-DECUSB)") (class "Default")
      (node (ref "C27") (pin "1") (pinfunction "1_1") (pintype "passive"))
      (node (ref "U1") (pin "AC5") (pinfunction "DECUSB_AC5") (pintype "power_in"))
    )
    (net (code "29") (name "Net-(U1-P0.00{slash}XL1)") (class "Default")
      (node (ref "C19") (pin "2") (pinfunction "2_2") (pintype "passive"))
      (node (ref "U1") (pin "D2") (pinfunction "P0.00/XL1_D2") (pintype "bidirectional"))
      (node (ref "Y1") (pin "1") (pinfunction "1_1") (pintype "passive"))
    )
    (net (code "30") (name "Net-(U1-P0.01{slash}XL2)") (class "Default")
      (node (ref "C20") (pin "2") (pinfunction "2_2") (pintype "passive"))
      (node (ref "U1") (pin "F2") (pinfunction "P0.01/XL2_F2") (pintype "bidirectional"))
      (node (ref "Y1") (pin "2") (pinfunction "2_2") (pintype "passive"))
    )
    (net (code "31") (name "Net-(U1-XC1)") (class "Default")
      (node (ref "C12") (pin "1") (pinfunction "1_1") (pintype "passive"))
      (node (ref "U1") (pin "B24") (pinfunction "XC1_B24") (pintype "input"))
      (node (ref "Y2") (pin "3") (pinfunction "HOT_3_3") (pintype "passive"))
    )
    (net (code "32") (name "Net-(U1-XC2)") (class "Default")
      (node (ref "C11") (pin "1") (pinfunction "1_1") (pintype "passive"))
      (node (ref "U1") (pin "A23") (pinfunction "XC2_A23") (pintype "input"))
      (node (ref "Y2") (pin "1") (pinfunction "HOT_1_1") (pintype "passive"))
    )
    (net (code "33") (name "Net-(U2-ILIM)") (class "Default")
      (node (ref "R3") (pin "2") (pinfunction "2_2") (pintype "passive"))
      (node (ref "U2") (pin "12") (pinfunction "ILIM_12") (pintype "input"))
    )
    (net (code "34") (name "Net-(U2-ISET)") (class "Default")
      (node (ref "R2") (pin "2") (pinfunction "2_2") (pintype "passive"))
      (node (ref "U2") (pin "16") (pinfunction "ISET_16") (pintype "bidirectional"))
    )
    (net (code "35") (name "Net-(U2-SYSOFF)") (class "Default")
      (node (ref "JP1") (pin "2") (pinfunction "2_2") (pintype "passive"))
      (node (ref "U2") (pin "15") (pinfunction "SYSOFF_15") (pintype "input"))
    )
    (net (code "36") (name "Net-(U2-~{CHG})") (class "Default")
      (node (ref "D4") (pin "C") (pinfunction "C_C") (pintype "passive"))
      (node (ref "U2") (pin "9") (pinfunction "~{CHG}_9") (pintype "output"))
    )
    (net (code "37") (name "Net-(U2-~{PGOOD})") (class "Default")
      (node (ref "D5") (pin "C") (pinfunction "C_C") (pintype "passive"))
      (node (ref "U2") (pin "7") (pinfunction "~{PGOOD}_7") (pintype "output"))
    )
    (net (code "38") (name "Net-(U3-EN)") (class "Default")
      (node (ref "R10") (pin "2") (pinfunction "2_2") (pintype "passive"))
      (node (ref "U3") (pin "3") (pinfunction "EN_3") (pintype "input"))
    )
    (net (code "39") (name "Net-(U6-EN)") (class "Default")
      (node (ref "JP2") (pin "2") (pinfunction "2_2") (pintype "passive"))
      (node (ref "U6") (pin "3") (pinfunction "EN_3") (pintype "input"))
    )
    (net (code "40") (name "Net-(U7-RF1)") (class "Default")
      (node (ref "C16") (pin "1") (pinfunction "1_1") (pintype "passive"))
      (node (ref "C18") (pin "2") (pinfunction "2_2") (pintype "passive"))
      (node (ref "U7") (pin "1") (pinfunction "RF1_1") (pintype "bidirectional"))
    )
    (net (code "41") (name "Net-(U7-RF2)") (class "Default")
      (node (ref "C39") (pin "1") (pinfunction "1_1") (pintype "passive"))
      (node (ref "L4") (pin "1") (pinfunction "1_1") (pintype "passive"))
      (node (ref "U7") (pin "3") (pinfunction "RF2_3") (pintype "bidirectional"))
    )
    (net (code "42") (name "Net-(U8-ANT)") (class "Default")
      (node (ref "L7") (pin "1") (pinfunction "1_1") (pintype "passive"))
      (node (ref "U8") (pin "10") (pinfunction "ANT_10") (pintype "passive"))
    )
    (net (code "43") (name "Net-(U8-RXEN)") (class "Default")
      (node (ref "R16") (pin "2") (pinfunction "2_2") (pintype "passive"))
      (node (ref "U8") (pin "6") (pinfunction "RXEN_6") (pintype "input"))
    )
    (net (code "44") (name "Net-(U8-TXEN)") (class "Default")
      (node (ref "R15") (pin "2") (pinfunction "2_2") (pintype "passive"))
      (node (ref "U8") (pin "5") (pinfunction "TXEN_5") (pintype "input"))
    )
    (net (code "45") (name "P0.02{slash}AIN0") (class "Default")
      (node (ref "J2") (pin "11") (pinfunction "11_11") (pintype "passive"))
      (node (ref "U1") (pin "A12") (pinfunction "P0.02/AIN0_A12") (pintype "bidirectional"))
    )
    (net (code "46") (name "P0.03{slash}AIN1") (class "Default")
      (node (ref "J2") (pin "8") (pinfunction "8_8") (pintype "passive"))
      (node (ref "U1") (pin "B13") (pinfunction "P0.03/AIN1_B13") (pintype "bidirectional"))
    )
    (net (code "47") (name "P0.04{slash}AIN2") (class "Default")
      (node (ref "U1") (pin "J1") (pinfunction "P0.04/AIN2_J1") (pintype "bidirectional"))
    )
    (net (code "48") (name "P0.05{slash}AIN3") (class "Default")
      (node (ref "U1") (pin "K2") (pinfunction "P0.05/AIN3_K2") (pintype "bidirectional"))
    )
    (net (code "49") (name "P0.06") (class "Default")
      (node (ref "J4") (pin "4") (pinfunction "4_4") (pintype "passive"))
      (node (ref "U1") (pin "L1") (pinfunction "P0.06_L1") (pintype "bidirectional"))
    )
    (net (code "50") (name "P0.07") (class "Default")
      (node (ref "U1") (pin "M2") (pinfunction "P0.07_M2") (pintype "bidirectional"))
    )
    (net (code "51") (name "P0.08") (class "Default")
      (node (ref "J4") (pin "5") (pinfunction "5_5") (pintype "passive"))
      (node (ref "U1") (pin "N1") (pinfunction "P0.08_N1") (pintype "bidirectional"))
    )
    (net (code "52") (name "P0.09{slash}NFC1") (class "Default")
      (node (ref "J4") (pin "11") (pinfunction "11_11") (pintype "passive"))
      (node (ref "U1") (pin "L24") (pinfunction "P0.09/NFC1_L24") (pintype "bidirectional"))
    )
    (net (code "53") (name "P0.10{slash}NFC2") (class "Default")
      (node (ref "J4") (pin "12") (pinfunction "12_12") (pintype "passive"))
      (node (ref "U1") (pin "J24") (pinfunction "P0.10/NFC2_J24") (pintype "bidirectional"))
    )
    (net (code "54") (name "P0.11") (class "Default")
      (node (ref "R11") (pin "2") (pinfunction "2_2") (pintype "passive"))
      (node (ref "U1") (pin "T2") (pinfunction "P0.11_T2") (pintype "bidirectional"))
    )
    (net (code "55") (name "P0.12") (class "Default")
      (node (ref "J4") (pin "7") (pinfunction "7_7") (pintype "passive"))
      (node (ref "U1") (pin "U1") (pinfunction "P0.12_U1") (pintype "bidirectional"))
    )
    (net (code "56") (name "P0.13") (class "Default")
      (node (ref "U1") (pin "AD8") (pinfunction "P0.13_AD8") (pintype "bidirectional"))
      (node (ref "U5") (pin "3") (pinfunction "SIO_2/WP_3") (pintype "passive"))
    )
    (net (code "57") (name "P0.14") (class "Default")
      (node (ref "U1") (pin "AC9") (pinfunction "P0.14_AC9") (pintype "bidirectional"))
    )
    (net (code "58") (name "P0.15") (class "Default")
      (node (ref "U1") (pin "AD10") (pinfunction "P0.15_AD10") (pintype "bidirectional"))
      (node (ref "U5") (pin "2") (pinfunction "SIO_1/SO_2") (pintype "passive"))
    )
    (net (code "59") (name "P0.16") (class "Default")
      (node (ref "U1") (pin "AC11") (pinfunction "P0.16_AC11") (pintype "bidirectional"))
    )
    (net (code "60") (name "P0.17") (class "Default")
      (node (ref "U1") (pin "AD12") (pinfunction "P0.17_AD12") (pintype "bidirectional"))
      (node (ref "U5") (pin "1") (pinfunction "CS_1") (pintype "passive"))
    )
    (net (code "61") (name "P0.18{slash}RESET") (class "Default")
      (node (ref "C5") (pin "1") (pinfunction "1_1") (pintype "passive"))
      (node (ref "J2") (pin "6") (pinfunction "6_6") (pintype "passive"))
      (node (ref "R4") (pin "1") (pinfunction "1_1") (pintype "passive"))
      (node (ref "RST") (pin "2") (pinfunction "2_2") (pintype "passive"))
      (node (ref "U1") (pin "AC13") (pinfunction "P0.18/~{RESET}_AC13") (pintype "bidirectional"))
    )
    (net (code "62") (name "P0.19") (class "Default")
      (node (ref "U1") (pin "AC15") (pinfunction "P0.19_AC15") (pintype "bidirectional"))
    )
    (net (code "63") (name "P0.20") (class "Default")
      (node (ref "U1") (pin "AD16") (pinfunction "P0.20_AD16") (pintype "bidirectional"))
      (node (ref "U5") (pin "7") (pinfunction "SIO_3/RST_7") (pintype "passive"))
    )
    (net (code "64") (name "P0.21") (class "Default")
      (node (ref "J4") (pin "8") (pinfunction "8_8") (pintype "passive"))
      (node (ref "U1") (pin "AC17") (pinfunction "P0.21_AC17") (pintype "bidirectional"))
    )
    (net (code "65") (name "P0.22") (class "Default")
      (node (ref "U1") (pin "AD18") (pinfunction "P0.22_AD18") (pintype "bidirectional"))
      (node (ref "U5") (pin "6") (pinfunction "SCLK_6") (pintype "passive"))
    )
    (net (code "66") (name "P0.23") (class "Default")
      (node (ref "J4") (pin "10") (pinfunction "10_10") (pintype "passive"))
      (node (ref "U1") (pin "AC19") (pinfunction "P0.23_AC19") (pintype "bidirectional"))
    )
    (net (code "67") (name "P0.24") (class "Default")
      (node (ref "U1") (pin "AD20") (pinfunction "P0.24_AD20") (pintype "bidirectional"))
      (node (ref "U5") (pin "5") (pinfunction "SIO_0/SI_5") (pintype "passive"))
    )
    (net (code "68") (name "P0.25") (class "Default")
      (node (ref "U1") (pin "AC21") (pinfunction "P0.25_AC21") (pintype "bidirectional"))
    )
    (net (code "69") (name "P0.26") (class "Default")
      (node (ref "J2") (pin "5") (pinfunction "5_5") (pintype "passive"))
      (node (ref "R7") (pin "2") (pinfunction "2_2") (pintype "passive"))
      (node (ref "U1") (pin "G1") (pinfunction "P0.26_G1") (pintype "bidirectional"))
    )
    (net (code "70") (name "P0.27") (class "Default")
      (node (ref "J2") (pin "4") (pinfunction "4_4") (pintype "passive"))
      (node (ref "R6") (pin "2") (pinfunction "2_2") (pintype "passive"))
      (node (ref "U1") (pin "H2") (pinfunction "P0.27_H2") (pintype "bidirectional"))
    )
    (net (code "71") (name "P0.28{slash}AIN4") (class "Default")
      (node (ref "J2") (pin "7") (pinfunction "7_7") (pintype "passive"))
      (node (ref "U1") (pin "B11") (pinfunction "P0.28/AIN4_B11") (pintype "bidirectional"))
    )
    (net (code "72") (name "P0.29{slash}AIN5") (class "Default")
      (node (ref "J2") (pin "10") (pinfunction "10_10") (pintype "passive"))
      (node (ref "U1") (pin "A10") (pinfunction "P0.29/AIN5_A10") (pintype "bidirectional"))
    )
    (net (code "73") (name "P0.30{slash}AIN6") (class "Default")
      (node (ref "U1") (pin "B9") (pinfunction "P0.30/AIN6_B9") (pintype "bidirectional"))
    )
    (net (code "74") (name "P0.30{slash}AIN7") (class "Default")
      (node (ref "J2") (pin "9") (pinfunction "9_9") (pintype "passive"))
      (node (ref "U1") (pin "A8") (pinfunction "P0.31/AIN7_A8") (pintype "bidirectional"))
    )
    (net (code "75") (name "P1.00") (class "Default")
      (node (ref "J4") (pin "9") (pinfunction "9_9") (pintype "passive"))
      (node (ref "U1") (pin "AD22") (pinfunction "P1.00_AD22") (pintype "bidirectional"))
    )
    (net (code "76") (name "P1.01") (class "Default")
      (node (ref "U1") (pin "Y23") (pinfunction "P1.01_Y23") (pintype "bidirectional"))
    )
    (net (code "77") (name "P1.02") (class "Default")
      (node (ref "JP2") (pin "1") (pinfunction "1_1") (pintype "passive"))
      (node (ref "U1") (pin "W24") (pinfunction "P1.02_W24") (pintype "bidirectional"))
    )
    (net (code "78") (name "P1.03") (class "Default")
      (node (ref "U1") (pin "V23") (pinfunction "P1.03_V23") (pintype "bidirectional"))
    )
    (net (code "79") (name "P1.04") (class "Default")
      (node (ref "R16") (pin "1") (pinfunction "1_1") (pintype "passive"))
      (node (ref "U1") (pin "U24") (pinfunction "P1.04_U24") (pintype "bidirectional"))
    )
    (net (code "80") (name "P1.05") (class "Default")
      (node (ref "R15") (pin "1") (pinfunction "1_1") (pintype "passive"))
      (node (ref "U1") (pin "T23") (pinfunction "P1.05_T23") (pintype "bidirectional"))
    )
    (net (code "81") (name "P1.06") (class "Default")
      (node (ref "U1") (pin "R24") (pinfunction "P1.06_R24") (pintype "bidirectional"))
      (node (ref "U7") (pin "6") (pinfunction "CTRL_6") (pintype "bidirectional"))
    )
    (net (code "82") (name "P1.07") (class "Default")
      (node (ref "U1") (pin "P23") (pinfunction "P1.07_P23") (pintype "bidirectional"))
    )
    (net (code "83") (name "P1.08") (class "Default")
      (node (ref "U1") (pin "P2") (pinfunction "P1.08_P2") (pintype "bidirectional"))
    )
    (net (code "84") (name "P1.09") (class "Default")
      (node (ref "J4") (pin "6") (pinfunction "6_6") (pintype "passive"))
      (node (ref "U1") (pin "R1") (pinfunction "P1.09_R1") (pintype "bidirectional"))
    )
    (net (code "85") (name "P1.10") (class "Default")
      (node (ref "BTN") (pin "2") (pinfunction "2_2") (pintype "passive"))
      (node (ref "R5") (pin "1") (pinfunction "1_1") (pintype "passive"))
      (node (ref "U1") (pin "A20") (pinfunction "P1.10_A20") (pintype "bidirectional"))
    )
    (net (code "86") (name "P1.11") (class "Default")
      (node (ref "U1") (pin "B19") (pinfunction "P1.11_B19") (pintype "bidirectional"))
    )
    (net (code "87") (name "P1.12") (class "Default")
      (node (ref "U1") (pin "B17") (pinfunction "P1.12_B17") (pintype "bidirectional"))
    )
    (net (code "88") (name "P1.13") (class "Default")
      (node (ref "J2") (pin "12") (pinfunction "12_12") (pintype "passive"))
      (node (ref "U1") (pin "A16") (pinfunction "P1.13_A16") (pintype "bidirectional"))
    )
    (net (code "89") (name "P1.14") (class "Default")
      (node (ref "U1") (pin "B15") (pinfunction "P1.14_B15") (pintype "bidirectional"))
    )
    (net (code "90") (name "P1.15") (class "Default")
      (node (ref "J2") (pin "13") (pinfunction "13_13") (pintype "passive"))
      (node (ref "U1") (pin "A14") (pinfunction "P1.15_A14") (pintype "bidirectional"))
    )
    (net (code "91") (name "RF") (class "Default")
      (node (ref "U1") (pin "H23") (pinfunction "ANT_H23") (pintype "bidirectional"))
      (node (ref "U7") (pin "5") (pinfunction "RFC_5") (pintype "bidirectional"))
    )
    (net (code "92") (name "RF'") (class "Default")
      (node (ref "C17") (pin "1") (pinfunction "1_1") (pintype "passive"))
      (node (ref "C18") (pin "1") (pinfunction "1_1") (pintype "passive"))
      (node (ref "U8") (pin "4") (pinfunction "TXRX_4") (pintype "bidirectional"))
    )
    (net (code "93") (name "SWDCLK") (class "Default")
      (node (ref "J4") (pin "14") (pinfunction "14_14") (pintype "passive"))
      (node (ref "U1") (pin "AA24") (pinfunction "SWDCLK_AA24") (pintype "input"))
    )
    (net (code "94") (name "SWDIO") (class "Default")
      (node (ref "J4") (pin "13") (pinfunction "13_13") (pintype "passive"))
      (node (ref "U1") (pin "AC24") (pinfunction "SWDIO_AC24") (pintype "input"))
    )
    (net (code "95") (name "VBUS") (class "Default")
      (node (ref "C24") (pin "1") (pinfunction "1_1") (pintype "passive"))
      (node (ref "C26") (pin "1") (pinfunction "1_1") (pintype "passive"))
      (node (ref "FB1") (pin "1") (pinfunction "1_1") (pintype "passive"))
      (node (ref "J3") (pin "A4_B9") (pinfunction "VBUS_A4_B9") (pintype "power_in"))
      (node (ref "J3") (pin "A9_B4") (pinfunction "VBUS_A9_B4") (pintype "power_in"))
      (node (ref "J4") (pin "1") (pinfunction "1_1") (pintype "passive"))
      (node (ref "R13") (pin "1") (pinfunction "1_1") (pintype "passive"))
      (node (ref "U4") (pin "4") (pinfunction "VCC_4") (pintype "passive"))
    )
    (net (code "96") (name "VBUS'") (class "Default")
      (node (ref "C25") (pin "1") (pinfunction "1_1") (pintype "passive"))
      (node (ref "FB1") (pin "2") (pinfunction "2_2") (pintype "passive"))
      (node (ref "U2") (pin "13") (pinfunction "IN_13") (pintype "input"))
    )
    (net (code "97") (name "VBUS''") (class "Default")
      (node (ref "C2") (pin "1") (pinfunction "1_1") (pintype "passive"))
      (node (ref "C3") (pin "1") (pinfunction "1_1") (pintype "passive"))
      (node (ref "C32") (pin "1") (pinfunction "1_1") (pintype "passive"))
      (node (ref "C4") (pin "1") (pinfunction "1_1") (pintype "passive"))
      (node (ref "J2") (pin "1") (pinfunction "1_1") (pintype "passive"))
      (node (ref "JP1") (pin "1") (pinfunction "1_1") (pintype "passive"))
      (node (ref "R10") (pin "1") (pinfunction "1_1") (pintype "passive"))
      (node (ref "R14") (pin "1") (pinfunction "1_1") (pintype "passive"))
      (node (ref "R8") (pin "2") (pinfunction "2_2") (pintype "passive"))
      (node (ref "R9") (pin "2") (pinfunction "2_2") (pintype "passive"))
      (node (ref "TP3") (pin "P$1") (pinfunction "1_P$1") (pintype "bidirectional"))
      (node (ref "U2") (pin "10") (pinfunction "OUT_10_10") (pintype "output"))
      (node (ref "U2") (pin "11") (pinfunction "OUT_11_11") (pintype "output"))
      (node (ref "U2") (pin "5") (pinfunction "EN2_5") (pintype "input"))
      (node (ref "U3") (pin "1") (pinfunction "IN_1") (pintype "input"))
      (node (ref "U6") (pin "1") (pinfunction "IN_1") (pintype "input"))
    )
    (net (code "98") (name "VBUS_NRF") (class "Default")
      (node (ref "C22") (pin "1") (pinfunction "1_1") (pintype "passive"))
      (node (ref "C23") (pin "1") (pinfunction "1_1") (pintype "passive"))
      (node (ref "R13") (pin "2") (pinfunction "2_2") (pintype "passive"))
      (node (ref "U1") (pin "AD2") (pinfunction "VBUS_AD2") (pintype "power_in"))
      (node (ref "U1") (pin "Y2") (pinfunction "VDDH_Y2") (pintype "power_in"))
    )
    (net (code "99") (name "VDD_FE") (class "Default")
      (node (ref "C33") (pin "1") (pinfunction "1_1") (pintype "passive"))
      (node (ref "C34") (pin "2") (pinfunction "2_2") (pintype "passive"))
      (node (ref "C35") (pin "2") (pinfunction "2_2") (pintype "passive"))
      (node (ref "C36") (pin "2") (pinfunction "2_2") (pintype "passive"))
      (node (ref "TP1") (pin "P$1") (pinfunction "1_P$1") (pintype "bidirectional"))
      (node (ref "U6") (pin "5") (pinfunction "OUT_5") (pintype "output"))
      (node (ref "U8") (pin "14") (pinfunction "VDD_14") (pintype "power_in"))
      (node (ref "U8") (pin "16") (pinfunction "VDD_16") (pintype "power_in"))
    )
    (net (code "100") (name "VDD_NRF") (class "Default")
      (node (ref "C10") (pin "1") (pinfunction "1_1") (pintype "passive"))
      (node (ref "C13") (pin "2") (pinfunction "2_2") (pintype "passive"))
      (node (ref "C21") (pin "1") (pinfunction "1_1") (pintype "passive"))
      (node (ref "C28") (pin "1") (pinfunction "1_1") (pintype "passive"))
      (node (ref "C29") (pin "1") (pinfunction "1_1") (pintype "passive"))
      (node (ref "C30") (pin "1") (pinfunction "1_1") (pintype "passive"))
      (node (ref "C31") (pin "1") (pinfunction "1_1") (pintype "passive"))
      (node (ref "C7") (pin "1") (pinfunction "1_1") (pintype "passive"))
      (node (ref "D2") (pin "A") (pinfunction "A_A") (pintype "passive"))
      (node (ref "D6") (pin "A") (pinfunction "A_A") (pintype "passive"))
      (node (ref "J2") (pin "3") (pinfunction "3_3") (pintype "passive"))
      (node (ref "J4") (pin "3") (pinfunction "3_3") (pintype "passive"))
      (node (ref "L3") (pin "1") (pinfunction "1_1") (pintype "passive"))
      (node (ref "R4") (pin "2") (pinfunction "2_2") (pintype "passive"))
      (node (ref "R5") (pin "2") (pinfunction "2_2") (pintype "passive"))
      (node (ref "R6") (pin "1") (pinfunction "1_1") (pintype "passive"))
      (node (ref "R7") (pin "1") (pinfunction "1_1") (pintype "passive"))
      (node (ref "TP2") (pin "P$1") (pinfunction "1_P$1") (pintype "bidirectional"))
      (node (ref "U1") (pin "A22") (pinfunction "VDD_A22") (pintype "power_in"))
      (node (ref "U1") (pin "AD14") (pinfunction "VDD_AD14") (pintype "power_in"))
      (node (ref "U1") (pin "AD23") (pinfunction "VDD_AD23") (pintype "power_in"))
      (node (ref "U1") (pin "B1") (pinfunction "VDD_B1") (pintype "power_in"))
      (node (ref "U1") (pin "W1") (pinfunction "VDD_W1") (pintype "power_in"))
      (node (ref "U3") (pin "5") (pinfunction "OUT_5") (pintype "output"))
      (node (ref "U5") (pin "8") (pinfunction "VCC_8") (pintype "power_in"))
      (node (ref "U7") (pin "4") (pinfunction "VDD_4") (pintype "bidirectional"))
    )
    (net (code "101") (name "unconnected-(J3-CC1-PadA5)") (class "Default")
      (node (ref "J3") (pin "A5") (pinfunction "CC1_A5") (pintype "bidirectional"))
    )
    (net (code "102") (name "unconnected-(J3-CC2-PadB5)") (class "Default")
      (node (ref "J3") (pin "B5") (pinfunction "CC2_B5") (pintype "bidirectional"))
    )
    (net (code "103") (name "unconnected-(J3-SBU1-PadA8)") (class "Default")
      (node (ref "J3") (pin "A8") (pinfunction "SBU1_A8") (pintype "bidirectional"))
    )
    (net (code "104") (name "unconnected-(J3-SBU2-PadB8)") (class "Default")
      (node (ref "J3") (pin "B8") (pinfunction "SBU2_B8") (pintype "bidirectional"))
    )
  )
)
